# ps2_com_ps2.net
KiCad netlist of a schematic drawn in EAGLE
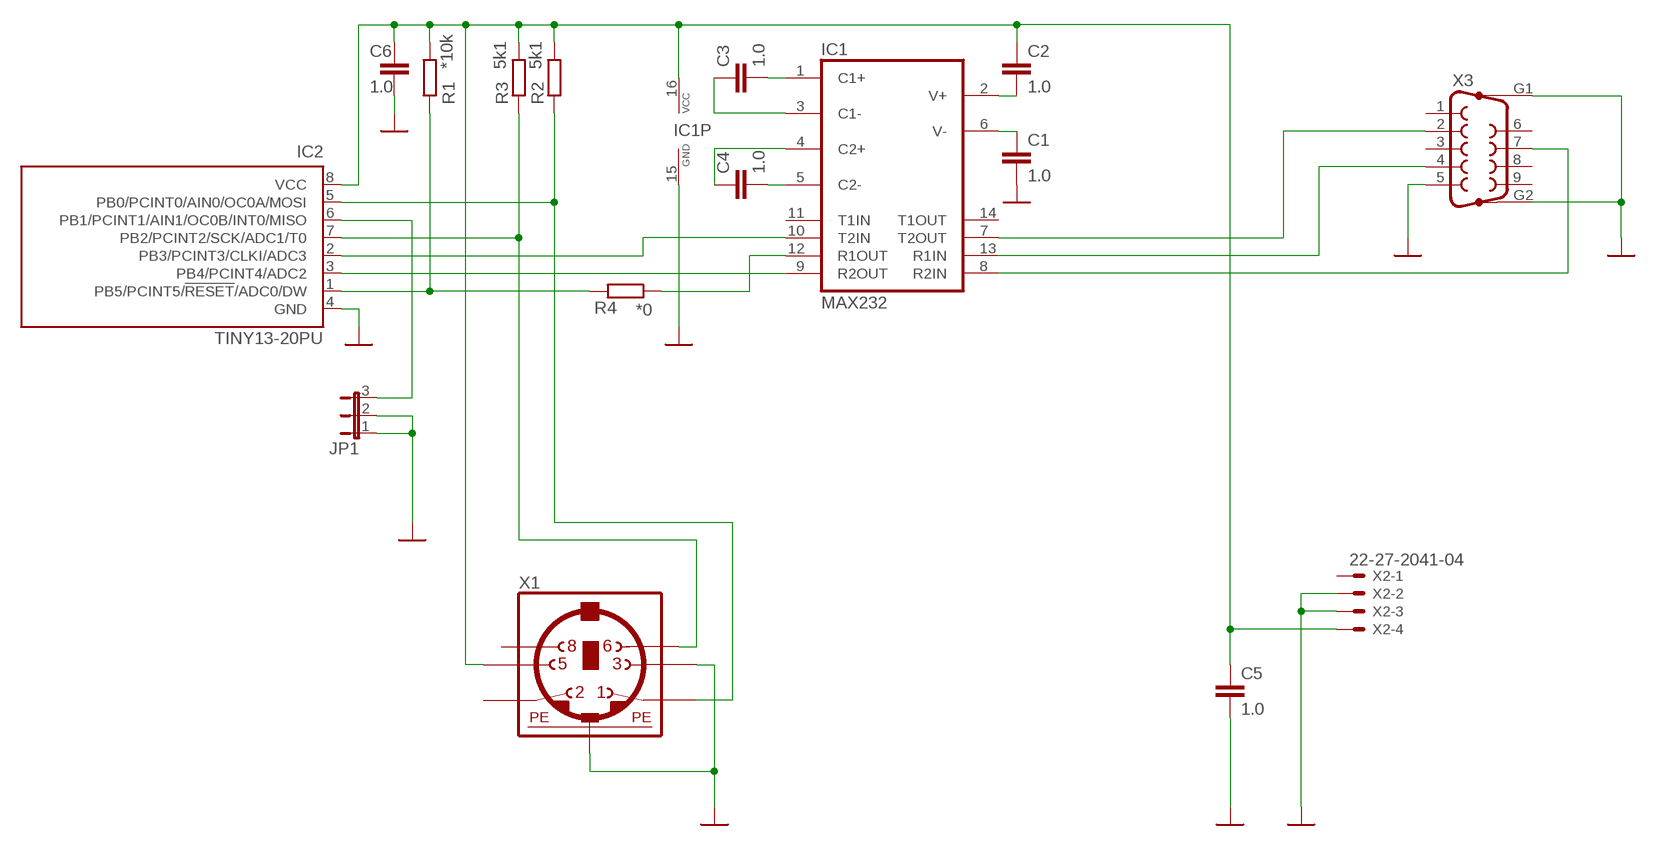
[diagram p0: schematic, sheet 1]

(export (version "E")
  (design (tool "Eeschema 10.0.6"))
  (components
    (comp (ref "C1")
      (value "1.0")
      (footprint "eagle-import:C025-025X050")
      (libsource (lib "eagle-import") (part "C-EU025-025X050"))
    )
    (comp (ref "C2")
      (value "1.0")
      (footprint "eagle-import:C025-025X050")
      (libsource (lib "eagle-import") (part "C-EU025-025X050"))
    )
    (comp (ref "C3")
      (value "1.0")
      (footprint "eagle-import:C025-025X050")
      (libsource (lib "eagle-import") (part "C-EU025-025X050"))
    )
    (comp (ref "C4")
      (value "1.0")
      (footprint "eagle-import:C025-025X050")
      (libsource (lib "eagle-import") (part "C-EU025-025X050"))
    )
    (comp (ref "C5")
      (value "1.0")
      (footprint "eagle-import:C025-025X050")
      (libsource (lib "eagle-import") (part "C-EU025-025X050"))
    )
    (comp (ref "C6")
      (value "1.0")
      (footprint "eagle-import:C025-025X050")
      (libsource (lib "eagle-import") (part "C-EU025-025X050"))
    )
    (comp (ref "IC1")
      (value "MAX232")
      (footprint "eagle-import:DIL16")
      (fields (field (name "MF") "MAXIM") (field (name "MPN") "MAX232ACPE+"))
      (libsource (lib "eagle-import") (part "MAX232"))
    )
    (comp (ref "IC2")
      (value "TINY13-20PU")
      (footprint "eagle-import:DIL08")
      (fields (field (name "MPN") "ATTINY13-20PU"))
      (libsource (lib "eagle-import") (part "TINY13PU-20"))
    )
    (comp (ref "JP1")
      (value "JP2E")
      (footprint "eagle-import:JP2")
      (libsource (lib "eagle-import") (part "JP2E"))
    )
    (comp (ref "R1")
      (value "*10k")
      (footprint "eagle-import:0204_7")
      (libsource (lib "eagle-import") (part "R-EU_0204/7"))
    )
    (comp (ref "R2")
      (value "5k1")
      (footprint "eagle-import:0204_5")
      (libsource (lib "eagle-import") (part "R-EU_0204/5"))
    )
    (comp (ref "R3")
      (value "5k1")
      (footprint "eagle-import:0204V")
      (libsource (lib "eagle-import") (part "R-EU_0204/2V"))
    )
    (comp (ref "R4")
      (value "*0")
      (footprint "eagle-import:0204V")
      (libsource (lib "eagle-import") (part "R-EU_0204/2V"))
    )
    (comp (ref "X1")
      (value "MINI_DIN_6")
      (footprint "eagle-import:M_DIN6")
      (libsource (lib "eagle-import") (part "MINI_DIN_6"))
    )
    (comp (ref "X2")
      (value "22-27-2041-04")
      (footprint "eagle-import:6410-04")
      (fields (field (name "MF") "MOLEX"))
      (libsource (lib "eagle-import") (part "22-?-0427-2041"))
    )
    (comp (ref "X3")
      (value "F09HP")
      (footprint "eagle-import:F09HP")
      (libsource (lib "eagle-import") (part "F09HP"))
    )
  )
  (nets
    (net (code "1") (name "GND") (class "Default")
      (node (ref "C1") (pin "2") (pinfunction "2_2") (pintype "passive"))
      (node (ref "C5") (pin "2") (pinfunction "2_2") (pintype "passive"))
      (node (ref "C6") (pin "2") (pinfunction "2_2") (pintype "passive"))
      (node (ref "IC1") (pin "15") (pinfunction "GND_15") (pintype "power_in"))
      (node (ref "IC2") (pin "4") (pinfunction "GND_4") (pintype "power_in"))
      (node (ref "JP1") (pin "1") (pinfunction "1_1") (pintype "passive"))
      (node (ref "JP1") (pin "2") (pinfunction "2_2") (pintype "passive"))
      (node (ref "X1") (pin "3") (pinfunction "3_3") (pintype "passive"))
      (node (ref "X1") (pin "SH1") (pinfunction "PE1_SH1") (pintype "power_in"))
      (node (ref "X1") (pin "SH2") (pinfunction "PE1_SH2") (pintype "power_in"))
      (node (ref "X1") (pin "SH3") (pinfunction "PE1_SH3") (pintype "power_in"))
      (node (ref "X2") (pin "2") (pinfunction "S_2") (pintype "passive"))
      (node (ref "X2") (pin "3") (pinfunction "S_3") (pintype "passive"))
      (node (ref "X3") (pin "5") (pinfunction "5_5") (pintype "passive"))
      (node (ref "X3") (pin "G1") (pinfunction "G1_G1") (pintype "passive"))
      (node (ref "X3") (pin "G2") (pinfunction "G2_G2") (pintype "passive"))
    )
    (net (code "2") (name "Net-(IC1A-C1+)") (class "Default")
      (node (ref "C3") (pin "2") (pinfunction "2_2") (pintype "passive"))
      (node (ref "IC1") (pin "1") (pinfunction "C1+_1") (pintype "bidirectional"))
    )
    (net (code "3") (name "Net-(IC1A-C1-)") (class "Default")
      (node (ref "C3") (pin "1") (pinfunction "1_1") (pintype "passive"))
      (node (ref "IC1") (pin "3") (pinfunction "C1-_3") (pintype "bidirectional"))
    )
    (net (code "4") (name "Net-(IC1A-C2+)") (class "Default")
      (node (ref "C4") (pin "1") (pinfunction "1_1") (pintype "passive"))
      (node (ref "IC1") (pin "4") (pinfunction "C2+_4") (pintype "bidirectional"))
    )
    (net (code "5") (name "Net-(IC1A-C2-)") (class "Default")
      (node (ref "C4") (pin "2") (pinfunction "2_2") (pintype "passive"))
      (node (ref "IC1") (pin "5") (pinfunction "C2-_5") (pintype "bidirectional"))
    )
    (net (code "6") (name "Net-(IC1A-R1IN)") (class "Default")
      (node (ref "IC1") (pin "13") (pinfunction "R1IN_13") (pintype "input"))
      (node (ref "X3") (pin "4") (pinfunction "4_4") (pintype "passive"))
    )
    (net (code "7") (name "Net-(IC1A-R1OUT)") (class "Default")
      (node (ref "IC1") (pin "12") (pinfunction "R1OUT_12") (pintype "output"))
      (node (ref "R4") (pin "1") (pinfunction "1_1") (pintype "passive"))
    )
    (net (code "8") (name "Net-(IC1A-R2IN)") (class "Default")
      (node (ref "IC1") (pin "8") (pinfunction "R2IN_8") (pintype "input"))
      (node (ref "X3") (pin "7") (pinfunction "7_7") (pintype "passive"))
    )
    (net (code "9") (name "Net-(IC1A-R2OUT)") (class "Default")
      (node (ref "IC1") (pin "9") (pinfunction "R2OUT_9") (pintype "output"))
      (node (ref "IC2") (pin "3") (pinfunction "PB4/PCINT4/ADC2_3") (pintype "bidirectional"))
    )
    (net (code "10") (name "Net-(IC1A-T2IN)") (class "Default")
      (node (ref "IC1") (pin "10") (pinfunction "T2IN_10") (pintype "input"))
      (node (ref "IC2") (pin "2") (pinfunction "PB3/PCINT3/CLKI/ADC3_2") (pintype "bidirectional"))
    )
    (net (code "11") (name "Net-(IC1A-T2OUT)") (class "Default")
      (node (ref "IC1") (pin "7") (pinfunction "T2OUT_7") (pintype "output"))
      (node (ref "X3") (pin "2") (pinfunction "2_2") (pintype "passive"))
    )
    (net (code "12") (name "Net-(IC1A-V+)") (class "Default")
      (node (ref "C2") (pin "2") (pinfunction "2_2") (pintype "passive"))
      (node (ref "IC1") (pin "2") (pinfunction "V+_2") (pintype "bidirectional"))
    )
    (net (code "13") (name "Net-(IC1A-V-)") (class "Default")
      (node (ref "C1") (pin "1") (pinfunction "1_1") (pintype "passive"))
      (node (ref "IC1") (pin "6") (pinfunction "V-_6") (pintype "bidirectional"))
    )
    (net (code "14") (name "Net-(IC1B-VCC)") (class "Default")
      (node (ref "C2") (pin "1") (pinfunction "1_1") (pintype "passive"))
      (node (ref "C5") (pin "1") (pinfunction "1_1") (pintype "passive"))
      (node (ref "C6") (pin "1") (pinfunction "1_1") (pintype "passive"))
      (node (ref "IC1") (pin "16") (pinfunction "VCC_16") (pintype "power_in"))
      (node (ref "IC2") (pin "8") (pinfunction "VCC_8") (pintype "power_in"))
      (node (ref "R1") (pin "2") (pinfunction "2_2") (pintype "passive"))
      (node (ref "R2") (pin "2") (pinfunction "2_2") (pintype "passive"))
      (node (ref "R3") (pin "2") (pinfunction "2_2") (pintype "passive"))
      (node (ref "X1") (pin "5") (pinfunction "5_5") (pintype "passive"))
      (node (ref "X2") (pin "4") (pinfunction "S_4") (pintype "passive"))
    )
    (net (code "15") (name "Net-(IC2-PB0{slash}PCINT0{slash}AIN0{slash}OC0A{slash}MOSI)") (class "Default")
      (node (ref "IC2") (pin "5") (pinfunction "PB0/PCINT0/AIN0/OC0A/MOSI_5") (pintype "bidirectional"))
      (node (ref "R2") (pin "1") (pinfunction "1_1") (pintype "passive"))
      (node (ref "X1") (pin "1") (pinfunction "1_1") (pintype "passive"))
    )
    (net (code "16") (name "Net-(IC2-PB1{slash}PCINT1{slash}AIN1{slash}OC0B{slash}INT0{slash}MISO)") (class "Default")
      (node (ref "IC2") (pin "6") (pinfunction "PB1/PCINT1/AIN1/OC0B/INT0/MISO_6") (pintype "bidirectional"))
      (node (ref "JP1") (pin "3") (pinfunction "3_3") (pintype "passive"))
    )
    (net (code "17") (name "Net-(IC2-PB2{slash}PCINT2{slash}SCK{slash}ADC1{slash}T0)") (class "Default")
      (node (ref "IC2") (pin "7") (pinfunction "PB2/PCINT2/SCK/ADC1/T0_7") (pintype "bidirectional"))
      (node (ref "R3") (pin "1") (pinfunction "1_1") (pintype "passive"))
      (node (ref "X1") (pin "6") (pinfunction "6_6") (pintype "passive"))
    )
    (net (code "18") (name "Net-(IC2-PB5{slash}PCINT5{slash}~{RESET}{slash}ADC0{slash}DW)") (class "Default")
      (node (ref "IC2") (pin "1") (pinfunction "PB5/PCINT5/~{RESET}/ADC0/DW_1") (pintype "bidirectional"))
      (node (ref "R1") (pin "1") (pinfunction "1_1") (pintype "passive"))
      (node (ref "R4") (pin "2") (pinfunction "2_2") (pintype "passive"))
    )
    (net (code "19") (name "unconnected-(IC1A-T1IN-Pad11)") (class "Default")
      (node (ref "IC1") (pin "11") (pinfunction "T1IN_11") (pintype "input"))
    )
    (net (code "20") (name "unconnected-(IC1A-T1OUT-Pad14)") (class "Default")
      (node (ref "IC1") (pin "14") (pinfunction "T1OUT_14") (pintype "output"))
    )
    (net (code "21") (name "unconnected-(X1-Pad2)") (class "Default")
      (node (ref "X1") (pin "2") (pinfunction "2_2") (pintype "passive"))
    )
    (net (code "22") (name "unconnected-(X1-Pad8)") (class "Default")
      (node (ref "X1") (pin "8") (pinfunction "8_8") (pintype "passive"))
    )
    (net (code "23") (name "unconnected-(X2A-S-Pad1)") (class "Default")
      (node (ref "X2") (pin "1") (pinfunction "S_1") (pintype "passive"))
    )
    (net (code "24") (name "unconnected-(X3-Pad1)") (class "Default")
      (node (ref "X3") (pin "1") (pinfunction "1_1") (pintype "passive"))
    )
    (net (code "25") (name "unconnected-(X3-Pad3)") (class "Default")
      (node (ref "X3") (pin "3") (pinfunction "3_3") (pintype "passive"))
    )
    (net (code "26") (name "unconnected-(X3-Pad6)") (class "Default")
      (node (ref "X3") (pin "6") (pinfunction "6_6") (pintype "passive"))
    )
    (net (code "27") (name "unconnected-(X3-Pad8)") (class "Default")
      (node (ref "X3") (pin "8") (pinfunction "8_8") (pintype "passive"))
    )
    (net (code "28") (name "unconnected-(X3-Pad9)") (class "Default")
      (node (ref "X3") (pin "9") (pinfunction "9_9") (pintype "passive"))
    )
  )
)
